# E4_TP2_Flyback.net
KiCad netlist of a schematic drawn in Altium Designer
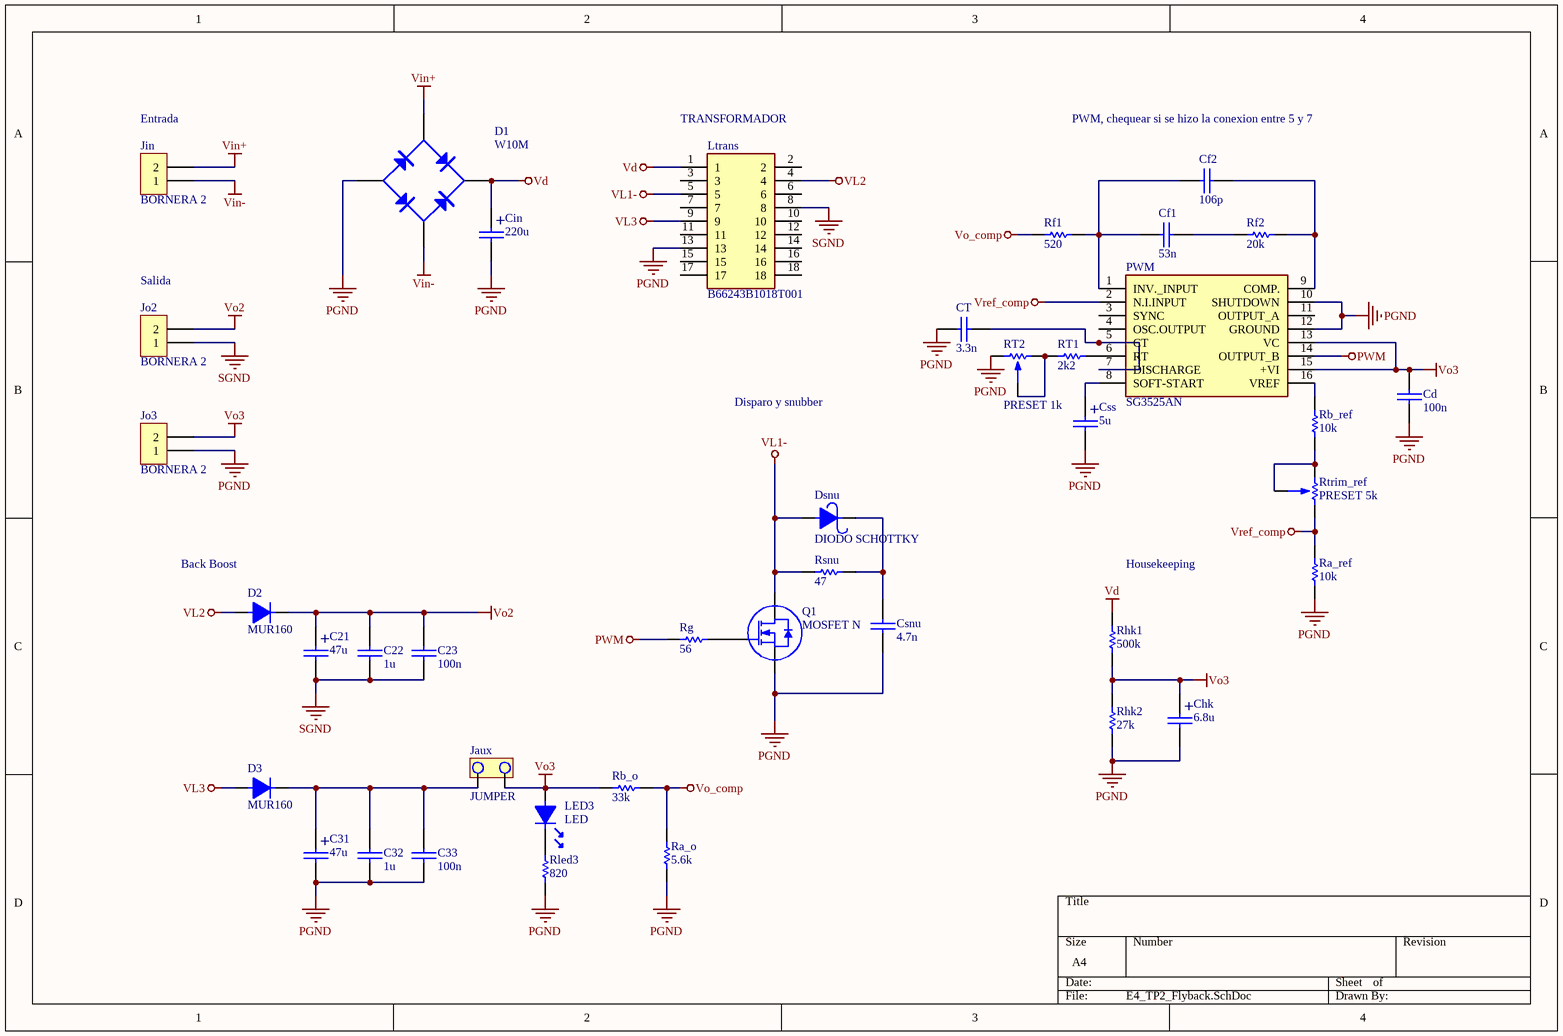
[diagram p0: E4_TP2_Flyback.SchDoc]

(export (version "E")
  (design (tool "Eeschema 10.0.6"))
  (components
    (comp (ref "C21") (value "47u") (footprint "CAP200RP") (libsource (lib "LIB PIO IX") (part "CAPPOL")))
    (comp (ref "C22") (value "1u") (footprint "CAP200") (libsource (lib "LIB PIO IX") (part "CAP")))
    (comp (ref "C23") (value "100n") (footprint "CAP100") (libsource (lib "LIB PIO IX") (part "CAP")))
    (comp (ref "C31") (value "47u") (footprint "CAP200RP") (libsource (lib "LIB PIO IX") (part "CAPPOL")))
    (comp (ref "C32") (value "1u") (footprint "CAP200") (libsource (lib "LIB PIO IX") (part "CAP")))
    (comp (ref "C33") (value "100n") (footprint "CAP100") (libsource (lib "LIB PIO IX") (part "CAP")))
    (comp (ref "Cd") (value "100n") (footprint "CAP100") (libsource (lib "LIB PIO IX") (part "CAP")))
    (comp (ref "Cf1") (value "53n") (footprint "CAP100") (libsource (lib "LIBEBAL") (part "CAP")))
    (comp (ref "Cf2") (value "106p") (footprint "CAP100") (libsource (lib "LIBEBAL") (part "CAP")))
    (comp (ref "Chk") (value "6.8u") (footprint "CAP100RP") (libsource (lib "LIBEBAL") (part "CAPPOL")))
    (comp (ref "Cin") (value "220u") (footprint "CAP200RP2") (libsource (lib "LIBEBAL") (part "CAPPOL")))
    (comp (ref "Csnu") (value "4.7n") (footprint "CAP200") (libsource (lib "LIBEBAL") (part "CAP")))
    (comp (ref "Css") (value "5u") (footprint "CAP100RP") (libsource (lib "LIB PIO IX") (part "CAPPOL")))
    (comp (ref "CT") (value "3.3n") (footprint "CAP100") (libsource (lib "LIB PIO IX") (part "CAP")))
    (comp (ref "D1") (value "W10M") (footprint "PUENTE - W10M") (libsource (lib "LIBEBAL") (part "PUENTE")))
    (comp (ref "D2") (value "MUR160") (footprint "DO41") (libsource (lib "LIB PIO IX") (part "DIODO")))
    (comp (ref "D3") (value "MUR160") (footprint "DO41") (libsource (lib "LIB PIO IX") (part "DIODO")))
    (comp (ref "Dsnu")
      (value "DIODO SCHOTTKY")
      (footprint "DO41")
      (libsource (lib "LIBEBAL") (part "DIODO SCHOTTKY"))
    )
    (comp (ref "Jaux") (value "JUMPER") (footprint "JUMPER2") (libsource (lib "LIBEBAL") (part "JUMPER")))
    (comp (ref "Jin")
      (value "BORNERA 2")
      (footprint "BORNERA2")
      (libsource (lib "LIBEBAL") (part "BORNERA 2"))
    )
    (comp (ref "Jo2")
      (value "BORNERA 2")
      (footprint "BORNERA2")
      (libsource (lib "LIBEBAL") (part "BORNERA 2"))
    )
    (comp (ref "Jo3")
      (value "BORNERA 2")
      (footprint "BORNERA2")
      (libsource (lib "LIBEBAL") (part "BORNERA 2"))
    )
    (comp (ref "LED3") (value "LED") (footprint "LED3") (libsource (lib "LIBEBAL") (part "LED")))
    (comp (ref "Ltrans")
      (value "B66243B1018T001")
      (footprint "SamacSys:B66243B1018T001")
      (description "Inductor")
      (libsource (lib "*") (part "B66243B1018T001"))
    )
    (comp (ref "PWM")
      (value "SG3525AN")
      (footprint "SamacSys:DIP850W50P254L2000H510Q16N")
      (description "Integrated Circuit")
      (fields (field (name "MOUSER PART NUMBER") "511-SG3525AN"))
      (libsource (lib "*") (part "SG3525AN"))
    )
    (comp (ref "Q1") (value "MOSFET N") (footprint "TO-220 V") (libsource (lib "LIBEBAL") (part "MOSFET N")))
    (comp (ref "Ra_o") (value "5.6k") (footprint "RES400") (libsource (lib "LIBEBAL") (part "RES")))
    (comp (ref "Ra_ref") (value "10k") (footprint "RES400") (libsource (lib "LIB PIO IX") (part "RES")))
    (comp (ref "Rb_o") (value "33k") (footprint "RES400") (libsource (lib "LIBEBAL") (part "RES")))
    (comp (ref "Rb_ref") (value "10k") (footprint "RES400") (libsource (lib "LIB PIO IX") (part "RES")))
    (comp (ref "Rf1") (value "520") (footprint "RES400") (libsource (lib "LIB PIO IX") (part "RES")))
    (comp (ref "Rf2") (value "20k") (footprint "RES400") (libsource (lib "LIB PIO IX") (part "RES")))
    (comp (ref "Rg") (value "56") (footprint "RES600") (libsource (lib "LIBEBAL") (part "RES")))
    (comp (ref "Rhk1") (value "500k") (footprint "RES400") (libsource (lib "LIBEBAL") (part "RES")))
    (comp (ref "Rhk2") (value "27k") (footprint "RES400") (libsource (lib "LIBEBAL") (part "RES")))
    (comp (ref "Rled3") (value "820") (footprint "RES400") (libsource (lib "LIBEBAL") (part "RES")))
    (comp (ref "Rsnu") (value "47") (footprint "RES600") (libsource (lib "LIBEBAL") (part "RES")))
    (comp (ref "RT1") (value "2k2") (footprint "RES400") (libsource (lib "LIB PIO IX") (part "RES")))
    (comp (ref "RT2")
      (value "PRESET 1k")
      (footprint "PRESET V")
      (libsource (lib "LIB PIO IX") (part "PRESET"))
    )
    (comp (ref "Rtrim_ref")
      (value "PRESET 5k")
      (footprint "PRESET V")
      (libsource (lib "LIBEBAL") (part "PRESET"))
    )
  )
  (nets
    (net (code "1") (name "Net-(C31-Pad1)") (class "Default")
      (node (ref "C31") (pin "1") (pinfunction "1_1") (pintype "passive"))
      (node (ref "C32") (pin "1") (pinfunction "1_1") (pintype "passive"))
      (node (ref "C33") (pin "1") (pinfunction "1_1") (pintype "passive"))
      (node (ref "D3") (pin "2") (pinfunction "2_2") (pintype "passive"))
      (node (ref "Jaux") (pin "2") (pinfunction "2_2") (pintype "passive"))
    )
    (net (code "2") (name "Net-(Cf1-Pad1)") (class "Default")
      (node (ref "Cf1") (pin "1") (pinfunction "1_1") (pintype "passive"))
      (node (ref "Rf2") (pin "1") (pinfunction "1_1") (pintype "passive"))
    )
    (net (code "3") (name "Net-(Csnu-Pad1)") (class "Default")
      (node (ref "Csnu") (pin "1") (pinfunction "1_1") (pintype "passive"))
      (node (ref "Dsnu") (pin "2") (pinfunction "2_2") (pintype "passive"))
      (node (ref "Rsnu") (pin "2") (pinfunction "2_2") (pintype "passive"))
    )
    (net (code "4") (name "Net-(LED3-Pad2)") (class "Default")
      (node (ref "LED3") (pin "2") (pinfunction "2_2") (pintype "passive"))
      (node (ref "Rled3") (pin "1") (pinfunction "1_1") (pintype "passive"))
    )
    (net (code "5") (name "Net-(PWM-COMP.)") (class "Default")
      (node (ref "Cf2") (pin "1") (pinfunction "1_1") (pintype "passive"))
      (node (ref "PWM") (pin "9") (pinfunction "COMP._9") (pintype "passive"))
      (node (ref "Rf2") (pin "2") (pinfunction "2_2") (pintype "passive"))
    )
    (net (code "6") (name "Net-(PWM-CT)") (class "Default")
      (node (ref "CT") (pin "1") (pinfunction "1_1") (pintype "passive"))
      (node (ref "PWM") (pin "5") (pinfunction "CT_5") (pintype "passive"))
      (node (ref "PWM") (pin "7") (pinfunction "DISCHARGE_7") (pintype "passive"))
    )
    (net (code "7") (name "Net-(PWM-INV._INPUT)") (class "Default")
      (node (ref "Cf1") (pin "2") (pinfunction "2_2") (pintype "passive"))
      (node (ref "Cf2") (pin "2") (pinfunction "2_2") (pintype "passive"))
      (node (ref "PWM") (pin "1") (pinfunction "INV._INPUT_1") (pintype "passive"))
      (node (ref "Rf1") (pin "2") (pinfunction "2_2") (pintype "passive"))
    )
    (net (code "8") (name "Net-(PWM-RT)") (class "Default")
      (node (ref "PWM") (pin "6") (pinfunction "RT_6") (pintype "passive"))
      (node (ref "RT1") (pin "2") (pinfunction "2_2") (pintype "passive"))
    )
    (net (code "9") (name "Net-(PWM-SOFT-START)") (class "Default")
      (node (ref "Css") (pin "1") (pinfunction "1_1") (pintype "passive"))
      (node (ref "PWM") (pin "8") (pinfunction "SOFT-START_8") (pintype "passive"))
    )
    (net (code "10") (name "Net-(PWM-VREF)") (class "Default")
      (node (ref "PWM") (pin "16") (pinfunction "VREF_16") (pintype "passive"))
      (node (ref "Rb_ref") (pin "1") (pinfunction "1_1") (pintype "passive"))
    )
    (net (code "11") (name "Net-(Q1-G)") (class "Default")
      (node (ref "Q1") (pin "1") (pinfunction "G_1") (pintype "passive"))
      (node (ref "Rg") (pin "2") (pinfunction "2_2") (pintype "passive"))
    )
    (net (code "12") (name "Net-(RT1-Pad1)") (class "Default")
      (node (ref "RT1") (pin "1") (pinfunction "1_1") (pintype "passive"))
      (node (ref "RT2") (pin "1") (pinfunction "1_1") (pintype "passive"))
      (node (ref "RT2") (pin "2") (pinfunction "2_2") (pintype "passive"))
    )
    (net (code "13") (name "Net-(Rb_ref-Pad2)") (class "Default")
      (node (ref "Rb_ref") (pin "2") (pinfunction "2_2") (pintype "passive"))
      (node (ref "Rtrim_ref") (pin "2") (pinfunction "2_2") (pintype "passive"))
      (node (ref "Rtrim_ref") (pin "3") (pinfunction "3_3") (pintype "passive"))
    )
    (net (code "14") (name "PGND") (class "Default")
      (node (ref "C31") (pin "2") (pinfunction "2_2") (pintype "passive"))
      (node (ref "C32") (pin "2") (pinfunction "2_2") (pintype "passive"))
      (node (ref "C33") (pin "2") (pinfunction "2_2") (pintype "passive"))
      (node (ref "CT") (pin "2") (pinfunction "2_2") (pintype "passive"))
      (node (ref "Cd") (pin "2") (pinfunction "2_2") (pintype "passive"))
      (node (ref "Chk") (pin "2") (pinfunction "2_2") (pintype "passive"))
      (node (ref "Cin") (pin "2") (pinfunction "2_2") (pintype "passive"))
      (node (ref "Csnu") (pin "2") (pinfunction "2_2") (pintype "passive"))
      (node (ref "Css") (pin "2") (pinfunction "2_2") (pintype "passive"))
      (node (ref "D1") (pin "3") (pinfunction "V-_3") (pintype "passive"))
      (node (ref "Jo3") (pin "1") (pinfunction "1_1") (pintype "passive"))
      (node (ref "Ltrans") (pin "13") (pinfunction "13_13") (pintype "passive"))
      (node (ref "PWM") (pin "10") (pinfunction "SHUTDOWN_10") (pintype "passive"))
      (node (ref "PWM") (pin "12") (pinfunction "GROUND_12") (pintype "passive"))
      (node (ref "Q1") (pin "3") (pinfunction "S_3") (pintype "passive"))
      (node (ref "RT2") (pin "3") (pinfunction "3_3") (pintype "passive"))
      (node (ref "Ra_o") (pin "2") (pinfunction "2_2") (pintype "passive"))
      (node (ref "Ra_ref") (pin "2") (pinfunction "2_2") (pintype "passive"))
      (node (ref "Rhk2") (pin "2") (pinfunction "2_2") (pintype "passive"))
      (node (ref "Rled3") (pin "2") (pinfunction "2_2") (pintype "passive"))
    )
    (net (code "15") (name "PWM") (class "Default")
      (node (ref "PWM") (pin "14") (pinfunction "OUTPUT_B_14") (pintype "passive"))
      (node (ref "Rg") (pin "1") (pinfunction "1_1") (pintype "passive"))
    )
    (net (code "16") (name "SGND") (class "Default")
      (node (ref "C21") (pin "2") (pinfunction "2_2") (pintype "passive"))
      (node (ref "C22") (pin "2") (pinfunction "2_2") (pintype "passive"))
      (node (ref "C23") (pin "2") (pinfunction "2_2") (pintype "passive"))
      (node (ref "Jo2") (pin "1") (pinfunction "1_1") (pintype "passive"))
      (node (ref "Ltrans") (pin "8") (pinfunction "8_8") (pintype "passive"))
    )
    (net (code "17") (name "VL1-") (class "Default")
      (node (ref "Dsnu") (pin "1") (pinfunction "1_1") (pintype "passive"))
      (node (ref "Ltrans") (pin "5") (pinfunction "5_5") (pintype "passive"))
      (node (ref "Q1") (pin "2") (pinfunction "D_2") (pintype "passive"))
      (node (ref "Rsnu") (pin "1") (pinfunction "1_1") (pintype "passive"))
    )
    (net (code "18") (name "VL2") (class "Default")
      (node (ref "D2") (pin "1") (pinfunction "1_1") (pintype "passive"))
      (node (ref "Ltrans") (pin "4") (pinfunction "4_4") (pintype "passive"))
    )
    (net (code "19") (name "VL3") (class "Default")
      (node (ref "D3") (pin "1") (pinfunction "1_1") (pintype "passive"))
      (node (ref "Ltrans") (pin "9") (pinfunction "9_9") (pintype "passive"))
    )
    (net (code "20") (name "Vd") (class "Default")
      (node (ref "Cin") (pin "1") (pinfunction "1_1") (pintype "passive"))
      (node (ref "D1") (pin "1") (pinfunction "V+_1") (pintype "passive"))
      (node (ref "Ltrans") (pin "1") (pinfunction "1_1") (pintype "passive"))
      (node (ref "Rhk1") (pin "1") (pinfunction "1_1") (pintype "passive"))
    )
    (net (code "21") (name "Vin+") (class "Default")
      (node (ref "D1") (pin "2") (pinfunction "AC_2") (pintype "passive"))
      (node (ref "Jin") (pin "2") (pinfunction "2_2") (pintype "passive"))
    )
    (net (code "22") (name "Vin-") (class "Default")
      (node (ref "D1") (pin "4") (pinfunction "AC_4") (pintype "passive"))
      (node (ref "Jin") (pin "1") (pinfunction "1_1") (pintype "passive"))
    )
    (net (code "23") (name "Vo2") (class "Default")
      (node (ref "C21") (pin "1") (pinfunction "1_1") (pintype "passive"))
      (node (ref "C22") (pin "1") (pinfunction "1_1") (pintype "passive"))
      (node (ref "C23") (pin "1") (pinfunction "1_1") (pintype "passive"))
      (node (ref "D2") (pin "2") (pinfunction "2_2") (pintype "passive"))
      (node (ref "Jo2") (pin "2") (pinfunction "2_2") (pintype "passive"))
    )
    (net (code "24") (name "Vo3") (class "Default")
      (node (ref "Cd") (pin "1") (pinfunction "1_1") (pintype "passive"))
      (node (ref "Chk") (pin "1") (pinfunction "1_1") (pintype "passive"))
      (node (ref "Jaux") (pin "1") (pinfunction "1_1") (pintype "passive"))
      (node (ref "Jo3") (pin "2") (pinfunction "2_2") (pintype "passive"))
      (node (ref "LED3") (pin "1") (pinfunction "1_1") (pintype "passive"))
      (node (ref "PWM") (pin "13") (pinfunction "VC_13") (pintype "passive"))
      (node (ref "PWM") (pin "15") (pinfunction "+VI_15") (pintype "passive"))
      (node (ref "Rb_o") (pin "2") (pinfunction "2_2") (pintype "passive"))
      (node (ref "Rhk1") (pin "2") (pinfunction "2_2") (pintype "passive"))
      (node (ref "Rhk2") (pin "1") (pinfunction "1_1") (pintype "passive"))
    )
    (net (code "25") (name "Vo_comp") (class "Default")
      (node (ref "Ra_o") (pin "1") (pinfunction "1_1") (pintype "passive"))
      (node (ref "Rb_o") (pin "1") (pinfunction "1_1") (pintype "passive"))
      (node (ref "Rf1") (pin "1") (pinfunction "1_1") (pintype "passive"))
    )
    (net (code "26") (name "Vref_comp") (class "Default")
      (node (ref "PWM") (pin "2") (pinfunction "N.I.INPUT_2") (pintype "passive"))
      (node (ref "Ra_ref") (pin "1") (pinfunction "1_1") (pintype "passive"))
      (node (ref "Rtrim_ref") (pin "1") (pinfunction "1_1") (pintype "passive"))
    )
    (net (code "27") (name "unconnected-(Ltrans-Pad2)") (class "Default")
      (node (ref "Ltrans") (pin "2") (pinfunction "2_2") (pintype "passive"))
    )
    (net (code "28") (name "unconnected-(Ltrans-Pad3)") (class "Default")
      (node (ref "Ltrans") (pin "3") (pinfunction "3_3") (pintype "passive"))
    )
    (net (code "29") (name "unconnected-(Ltrans-Pad6)") (class "Default")
      (node (ref "Ltrans") (pin "6") (pinfunction "6_6") (pintype "passive"))
    )
    (net (code "30") (name "unconnected-(Ltrans-Pad7)") (class "Default")
      (node (ref "Ltrans") (pin "7") (pinfunction "7_7") (pintype "passive"))
    )
    (net (code "31") (name "unconnected-(Ltrans-Pad10)") (class "Default")
      (node (ref "Ltrans") (pin "10") (pinfunction "10_10") (pintype "passive"))
    )
    (net (code "32") (name "unconnected-(Ltrans-Pad11)") (class "Default")
      (node (ref "Ltrans") (pin "11") (pinfunction "11_11") (pintype "passive"))
    )
    (net (code "33") (name "unconnected-(Ltrans-Pad12)") (class "Default")
      (node (ref "Ltrans") (pin "12") (pinfunction "12_12") (pintype "passive"))
    )
    (net (code "34") (name "unconnected-(Ltrans-Pad14)") (class "Default")
      (node (ref "Ltrans") (pin "14") (pinfunction "14_14") (pintype "passive"))
    )
    (net (code "35") (name "unconnected-(Ltrans-Pad15)") (class "Default")
      (node (ref "Ltrans") (pin "15") (pinfunction "15_15") (pintype "passive"))
    )
    (net (code "36") (name "unconnected-(Ltrans-Pad16)") (class "Default")
      (node (ref "Ltrans") (pin "16") (pinfunction "16_16") (pintype "passive"))
    )
    (net (code "37") (name "unconnected-(Ltrans-Pad17)") (class "Default")
      (node (ref "Ltrans") (pin "17") (pinfunction "17_17") (pintype "passive"))
    )
    (net (code "38") (name "unconnected-(Ltrans-Pad18)") (class "Default")
      (node (ref "Ltrans") (pin "18") (pinfunction "18_18") (pintype "passive"))
    )
    (net (code "39") (name "unconnected-(PWM-OSC.OUTPUT-Pad4)") (class "Default")
      (node (ref "PWM") (pin "4") (pinfunction "OSC.OUTPUT_4") (pintype "passive"))
    )
    (net (code "40") (name "unconnected-(PWM-OUTPUT_A-Pad11)") (class "Default")
      (node (ref "PWM") (pin "11") (pinfunction "OUTPUT_A_11") (pintype "passive"))
    )
    (net (code "41") (name "unconnected-(PWM-SYNC-Pad3)") (class "Default")
      (node (ref "PWM") (pin "3") (pinfunction "SYNC_3") (pintype "passive"))
    )
  )
)
